# IO_Top_BOARD.net
KiCad netlist of a schematic drawn in EAGLE
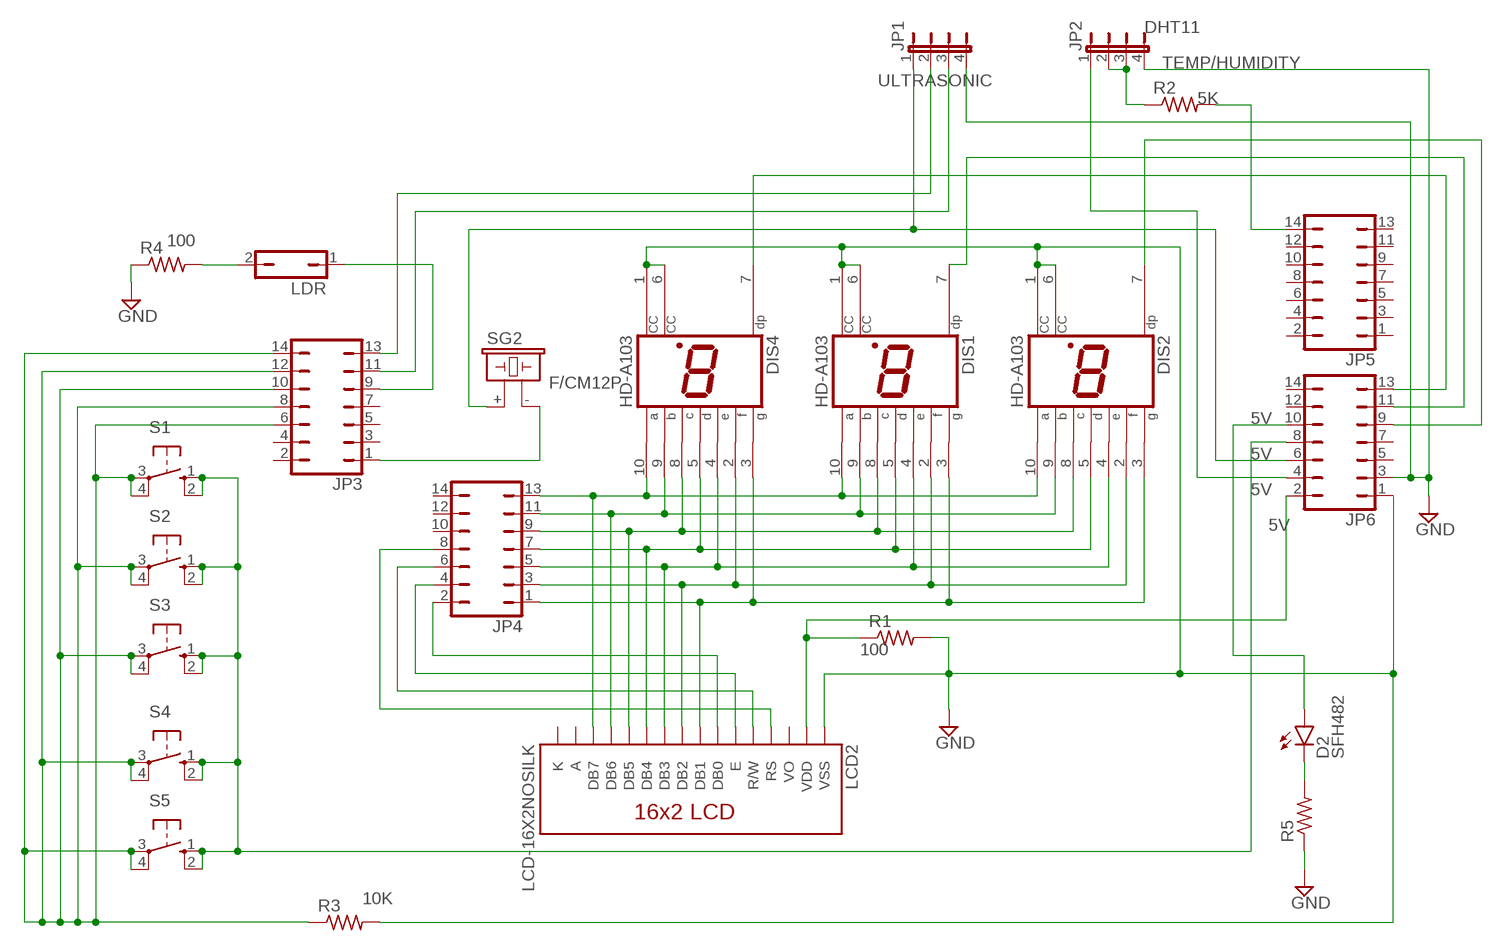
[diagram p0: schematic, sheet 1]

(export (version "E")
  (design (tool "Eeschema 10.0.6"))
  (components
    (comp (ref "D2")
      (value "SFH482")
      (footprint "eagle-import:SFH482")
      (libsource (lib "eagle-import") (part "SFH482"))
    )
    (comp (ref "DIS1")
      (value "HD-A103")
      (footprint "eagle-import:HDSP-A")
      (libsource (lib "eagle-import") (part "HD-A103"))
    )
    (comp (ref "DIS2")
      (value "HD-A103")
      (footprint "eagle-import:HDSP-A")
      (libsource (lib "eagle-import") (part "HD-A103"))
    )
    (comp (ref "DIS4")
      (value "HD-A103")
      (footprint "eagle-import:HDSP-A")
      (libsource (lib "eagle-import") (part "HD-A103"))
    )
    (comp (ref "JP1")
      (value "JP4E")
      (footprint "eagle-import:JP4")
      (libsource (lib "eagle-import") (part "JP4E"))
    )
    (comp (ref "JP2")
      (value "JP4E")
      (footprint "eagle-import:JP4")
      (libsource (lib "eagle-import") (part "JP4E"))
    )
    (comp (ref "JP3")
      (value "JP7Q")
      (footprint "eagle-import:JP7Q")
      (libsource (lib "eagle-import") (part "JP7Q"))
    )
    (comp (ref "JP4")
      (value "JP7Q")
      (footprint "eagle-import:JP7Q")
      (libsource (lib "eagle-import") (part "JP7Q"))
    )
    (comp (ref "JP5")
      (value "JP7Q")
      (footprint "eagle-import:JP7Q")
      (libsource (lib "eagle-import") (part "JP7Q"))
    )
    (comp (ref "JP6")
      (value "JP7Q")
      (footprint "eagle-import:JP7Q")
      (libsource (lib "eagle-import") (part "JP7Q"))
    )
    (comp (ref "LCD2")
      (value "LCD-16X2NOSILK")
      (footprint "eagle-import:LCD-16X2_NOSILK")
      (libsource (lib "eagle-import") (part "LCD-16X2NOSILK"))
    )
    (comp (ref "LDR")
      (value "JP1Q")
      (footprint "eagle-import:JP1")
      (libsource (lib "eagle-import") (part "JP1Q"))
    )
    (comp (ref "R1")
      (value "R-US_0204/2V")
      (footprint "eagle-import:0204V")
      (libsource (lib "eagle-import") (part "R-US_0204/2V"))
    )
    (comp (ref "R2")
      (value "R-US_0204/2V")
      (footprint "eagle-import:0204V")
      (libsource (lib "eagle-import") (part "R-US_0204/2V"))
    )
    (comp (ref "R3")
      (value "R-US_0204/2V")
      (footprint "eagle-import:0204V")
      (libsource (lib "eagle-import") (part "R-US_0204/2V"))
    )
    (comp (ref "R4")
      (value "R-US_0204/2V")
      (footprint "eagle-import:0204V")
      (libsource (lib "eagle-import") (part "R-US_0204/2V"))
    )
    (comp (ref "R5")
      (value "R-US_0204/2V")
      (footprint "eagle-import:0204V")
      (libsource (lib "eagle-import") (part "R-US_0204/2V"))
    )
    (comp (ref "S1")
      (value "10-XX")
      (footprint "eagle-import:B3F-10XX")
      (fields (field (name "MPN") "B3F-1000"))
      (libsource (lib "eagle-import") (part "10-XX"))
    )
    (comp (ref "S2")
      (value "10-XX")
      (footprint "eagle-import:B3F-10XX")
      (fields (field (name "MPN") "B3F-1000"))
      (libsource (lib "eagle-import") (part "10-XX"))
    )
    (comp (ref "S3")
      (value "10-XX")
      (footprint "eagle-import:B3F-10XX")
      (fields (field (name "MPN") "B3F-1000"))
      (libsource (lib "eagle-import") (part "10-XX"))
    )
    (comp (ref "S4")
      (value "10-XX")
      (footprint "eagle-import:B3F-10XX")
      (fields (field (name "MPN") "B3F-1000"))
      (libsource (lib "eagle-import") (part "10-XX"))
    )
    (comp (ref "S5")
      (value "10-XX")
      (footprint "eagle-import:B3F-10XX")
      (fields (field (name "MPN") "B3F-1000"))
      (libsource (lib "eagle-import") (part "10-XX"))
    )
    (comp (ref "SG2")
      (value "F/CM12P")
      (footprint "eagle-import:F_CM12P")
      (libsource (lib "eagle-import") (part "F/CM12P"))
    )
  )
  (nets
    (net (code "1") (name "/5V") (class "Default")
      (node (ref "JP1") (pin "1") (pinfunction "1_1") (pintype "passive"))
      (node (ref "JP6") (pin "6") (pinfunction "6_6") (pintype "passive"))
      (node (ref "SG2") (pin "+") (pinfunction "1_+") (pintype "passive"))
    )
    (net (code "2") (name "/A") (class "Default")
      (node (ref "LCD2") (pin "15") (pinfunction "A_15") (pintype "power_in"))
    )
    (net (code "3") (name "/K") (class "Default")
      (node (ref "LCD2") (pin "16") (pinfunction "K_16") (pintype "power_in"))
    )
    (net (code "4") (name "GND") (class "Default")
      (node (ref "DIS1") (pin "1") (pinfunction "CC_1") (pintype "passive"))
      (node (ref "DIS1") (pin "6") (pinfunction "CC_6") (pintype "passive"))
      (node (ref "DIS2") (pin "1") (pinfunction "CC_1") (pintype "passive"))
      (node (ref "DIS2") (pin "6") (pinfunction "CC_6") (pintype "passive"))
      (node (ref "DIS4") (pin "1") (pinfunction "CC_1") (pintype "passive"))
      (node (ref "DIS4") (pin "6") (pinfunction "CC_6") (pintype "passive"))
      (node (ref "JP1") (pin "4") (pinfunction "4_4") (pintype "passive"))
      (node (ref "JP2") (pin "4") (pinfunction "4_4") (pintype "passive"))
      (node (ref "JP6") (pin "1") (pinfunction "1_1") (pintype "passive"))
      (node (ref "JP6") (pin "3") (pinfunction "3_3") (pintype "passive"))
      (node (ref "LCD2") (pin "1") (pinfunction "VSS_1") (pintype "power_in"))
      (node (ref "R1") (pin "2") (pinfunction "2_2") (pintype "passive"))
      (node (ref "R3") (pin "2") (pinfunction "2_2") (pintype "passive"))
      (node (ref "R4") (pin "1") (pinfunction "1_1") (pintype "passive"))
      (node (ref "R5") (pin "1") (pinfunction "1_1") (pintype "passive"))
    )
    (net (code "5") (name "Net-(D2-C)") (class "Default")
      (node (ref "D2") (pin "K") (pinfunction "C_K") (pintype "passive"))
      (node (ref "R5") (pin "2") (pinfunction "2_2") (pintype "passive"))
    )
    (net (code "6") (name "Net-(D2-PadA)") (class "Default")
      (node (ref "D2") (pin "A") (pinfunction "A_A") (pintype "passive"))
      (node (ref "JP6") (pin "10") (pinfunction "10_10") (pintype "passive"))
    )
    (net (code "7") (name "Net-(DIS1-A)") (class "Default")
      (node (ref "DIS1") (pin "10") (pinfunction "A_10") (pintype "passive"))
      (node (ref "DIS2") (pin "10") (pinfunction "A_10") (pintype "passive"))
      (node (ref "DIS4") (pin "10") (pinfunction "A_10") (pintype "passive"))
      (node (ref "JP4") (pin "13") (pinfunction "13_13") (pintype "passive"))
      (node (ref "LCD2") (pin "14") (pinfunction "DB7_14") (pintype "bidirectional"))
    )
    (net (code "8") (name "Net-(DIS1-B)") (class "Default")
      (node (ref "DIS1") (pin "9") (pinfunction "B_9") (pintype "passive"))
      (node (ref "DIS2") (pin "9") (pinfunction "B_9") (pintype "passive"))
      (node (ref "DIS4") (pin "9") (pinfunction "B_9") (pintype "passive"))
      (node (ref "JP4") (pin "11") (pinfunction "11_11") (pintype "passive"))
      (node (ref "LCD2") (pin "13") (pinfunction "DB6_13") (pintype "bidirectional"))
    )
    (net (code "9") (name "Net-(DIS1-C)") (class "Default")
      (node (ref "DIS1") (pin "8") (pinfunction "C_8") (pintype "passive"))
      (node (ref "DIS2") (pin "8") (pinfunction "C_8") (pintype "passive"))
      (node (ref "DIS4") (pin "8") (pinfunction "C_8") (pintype "passive"))
      (node (ref "JP4") (pin "9") (pinfunction "9_9") (pintype "passive"))
      (node (ref "LCD2") (pin "12") (pinfunction "DB5_12") (pintype "bidirectional"))
    )
    (net (code "10") (name "Net-(DIS1-D)") (class "Default")
      (node (ref "DIS1") (pin "5") (pinfunction "D_5") (pintype "passive"))
      (node (ref "DIS2") (pin "5") (pinfunction "D_5") (pintype "passive"))
      (node (ref "DIS4") (pin "5") (pinfunction "D_5") (pintype "passive"))
      (node (ref "JP4") (pin "7") (pinfunction "7_7") (pintype "passive"))
      (node (ref "LCD2") (pin "11") (pinfunction "DB4_11") (pintype "bidirectional"))
    )
    (net (code "11") (name "Net-(DIS1-DP)") (class "Default")
      (node (ref "DIS1") (pin "7") (pinfunction "DP_7") (pintype "passive"))
      (node (ref "JP6") (pin "11") (pinfunction "11_11") (pintype "passive"))
    )
    (net (code "12") (name "Net-(DIS1-E)") (class "Default")
      (node (ref "DIS1") (pin "4") (pinfunction "E_4") (pintype "passive"))
      (node (ref "DIS2") (pin "4") (pinfunction "E_4") (pintype "passive"))
      (node (ref "DIS4") (pin "4") (pinfunction "E_4") (pintype "passive"))
      (node (ref "JP4") (pin "5") (pinfunction "5_5") (pintype "passive"))
      (node (ref "LCD2") (pin "10") (pinfunction "DB3_10") (pintype "bidirectional"))
    )
    (net (code "13") (name "Net-(DIS1-F)") (class "Default")
      (node (ref "DIS1") (pin "2") (pinfunction "F_2") (pintype "passive"))
      (node (ref "DIS2") (pin "2") (pinfunction "F_2") (pintype "passive"))
      (node (ref "DIS4") (pin "2") (pinfunction "F_2") (pintype "passive"))
      (node (ref "JP4") (pin "3") (pinfunction "3_3") (pintype "passive"))
      (node (ref "LCD2") (pin "9") (pinfunction "DB2_9") (pintype "bidirectional"))
    )
    (net (code "14") (name "Net-(DIS1-G)") (class "Default")
      (node (ref "DIS1") (pin "3") (pinfunction "G_3") (pintype "passive"))
      (node (ref "DIS2") (pin "3") (pinfunction "G_3") (pintype "passive"))
      (node (ref "DIS4") (pin "3") (pinfunction "G_3") (pintype "passive"))
      (node (ref "JP4") (pin "1") (pinfunction "1_1") (pintype "passive"))
      (node (ref "LCD2") (pin "8") (pinfunction "DB1_8") (pintype "bidirectional"))
    )
    (net (code "15") (name "Net-(DIS2-DP)") (class "Default")
      (node (ref "DIS2") (pin "7") (pinfunction "DP_7") (pintype "passive"))
      (node (ref "JP6") (pin "9") (pinfunction "9_9") (pintype "passive"))
    )
    (net (code "16") (name "Net-(DIS4-DP)") (class "Default")
      (node (ref "DIS4") (pin "7") (pinfunction "DP_7") (pintype "passive"))
      (node (ref "JP6") (pin "13") (pinfunction "13_13") (pintype "passive"))
    )
    (net (code "17") (name "Net-(JP1-Pad2)") (class "Default")
      (node (ref "JP1") (pin "2") (pinfunction "2_2") (pintype "passive"))
      (node (ref "JP3") (pin "13") (pinfunction "13_13") (pintype "passive"))
    )
    (net (code "18") (name "Net-(JP1-Pad3)") (class "Default")
      (node (ref "JP1") (pin "3") (pinfunction "3_3") (pintype "passive"))
      (node (ref "JP3") (pin "11") (pinfunction "11_11") (pintype "passive"))
    )
    (net (code "19") (name "Net-(JP2-Pad1)") (class "Default")
      (node (ref "JP2") (pin "1") (pinfunction "1_1") (pintype "passive"))
      (node (ref "JP6") (pin "4") (pinfunction "4_4") (pintype "passive"))
    )
    (net (code "20") (name "Net-(JP2-Pad2)") (class "Default")
      (node (ref "JP2") (pin "2") (pinfunction "2_2") (pintype "passive"))
      (node (ref "JP2") (pin "3") (pinfunction "3_3") (pintype "passive"))
      (node (ref "R2") (pin "1") (pinfunction "1_1") (pintype "passive"))
    )
    (net (code "21") (name "Net-(JP3-Pad9)") (class "Default")
      (node (ref "JP3") (pin "9") (pinfunction "9_9") (pintype "passive"))
      (node (ref "LDR") (pin "1") (pinfunction "1_1") (pintype "passive"))
    )
    (net (code "22") (name "Net-(JP5-Pad14)") (class "Default")
      (node (ref "JP5") (pin "14") (pinfunction "14_14") (pintype "passive"))
      (node (ref "R2") (pin "2") (pinfunction "2_2") (pintype "passive"))
    )
    (net (code "23") (name "Net-(LCD2-DB0)") (class "Default")
      (node (ref "JP4") (pin "2") (pinfunction "2_2") (pintype "passive"))
      (node (ref "LCD2") (pin "7") (pinfunction "DB0_7") (pintype "bidirectional"))
    )
    (net (code "24") (name "Net-(LCD2-E)") (class "Default")
      (node (ref "JP4") (pin "4") (pinfunction "4_4") (pintype "passive"))
      (node (ref "LCD2") (pin "6") (pinfunction "E_6") (pintype "input"))
    )
    (net (code "25") (name "Net-(LCD2-RS)") (class "Default")
      (node (ref "JP4") (pin "8") (pinfunction "8_8") (pintype "passive"))
      (node (ref "LCD2") (pin "4") (pinfunction "RS_4") (pintype "input"))
    )
    (net (code "26") (name "Net-(LCD2-R{slash}W)") (class "Default")
      (node (ref "JP4") (pin "6") (pinfunction "6_6") (pintype "passive"))
      (node (ref "LCD2") (pin "5") (pinfunction "R/W_5") (pintype "input"))
    )
    (net (code "27") (name "Net-(LCD2-VDD)") (class "Default")
      (node (ref "JP6") (pin "2") (pinfunction "2_2") (pintype "passive"))
      (node (ref "LCD2") (pin "2") (pinfunction "VDD_2") (pintype "power_in"))
      (node (ref "R1") (pin "1") (pinfunction "1_1") (pintype "passive"))
    )
    (net (code "28") (name "Net-(LDR-Pad2)") (class "Default")
      (node (ref "LDR") (pin "2") (pinfunction "2_2") (pintype "passive"))
      (node (ref "R4") (pin "2") (pinfunction "2_2") (pintype "passive"))
    )
    (net (code "29") (name "Net-(S1-P)") (class "Default")
      (node (ref "JP3") (pin "10") (pinfunction "10_10") (pintype "passive"))
      (node (ref "JP3") (pin "12") (pinfunction "12_12") (pintype "passive"))
      (node (ref "JP3") (pin "14") (pinfunction "14_14") (pintype "passive"))
      (node (ref "JP3") (pin "6") (pinfunction "6_6") (pintype "passive"))
      (node (ref "JP3") (pin "8") (pinfunction "8_8") (pintype "passive"))
      (node (ref "R3") (pin "1") (pinfunction "1_1") (pintype "passive"))
      (node (ref "S1") (pin "3") (pinfunction "P_3") (pintype "passive"))
      (node (ref "S1") (pin "4") (pinfunction "P1_4") (pintype "passive"))
      (node (ref "S2") (pin "3") (pinfunction "P_3") (pintype "passive"))
      (node (ref "S2") (pin "4") (pinfunction "P1_4") (pintype "passive"))
      (node (ref "S3") (pin "3") (pinfunction "P_3") (pintype "passive"))
      (node (ref "S3") (pin "4") (pinfunction "P1_4") (pintype "passive"))
      (node (ref "S4") (pin "3") (pinfunction "P_3") (pintype "passive"))
      (node (ref "S4") (pin "4") (pinfunction "P1_4") (pintype "passive"))
      (node (ref "S5") (pin "3") (pinfunction "P_3") (pintype "passive"))
      (node (ref "S5") (pin "4") (pinfunction "P1_4") (pintype "passive"))
    )
    (net (code "30") (name "Net-(S1-S)") (class "Default")
      (node (ref "JP6") (pin "8") (pinfunction "8_8") (pintype "passive"))
      (node (ref "S1") (pin "1") (pinfunction "S_1") (pintype "passive"))
      (node (ref "S1") (pin "2") (pinfunction "S1_2") (pintype "passive"))
      (node (ref "S2") (pin "1") (pinfunction "S_1") (pintype "passive"))
      (node (ref "S2") (pin "2") (pinfunction "S1_2") (pintype "passive"))
      (node (ref "S3") (pin "1") (pinfunction "S_1") (pintype "passive"))
      (node (ref "S3") (pin "2") (pinfunction "S1_2") (pintype "passive"))
      (node (ref "S4") (pin "1") (pinfunction "S_1") (pintype "passive"))
      (node (ref "S4") (pin "2") (pinfunction "S1_2") (pintype "passive"))
      (node (ref "S5") (pin "1") (pinfunction "S_1") (pintype "passive"))
      (node (ref "S5") (pin "2") (pinfunction "S1_2") (pintype "passive"))
    )
    (net (code "31") (name "Net-(SG2-2)") (class "Default")
      (node (ref "JP3") (pin "1") (pinfunction "1_1") (pintype "passive"))
      (node (ref "SG2") (pin "-") (pinfunction "2_-") (pintype "passive"))
    )
    (net (code "32") (name "unconnected-(JP3-Pad2)") (class "Default")
      (node (ref "JP3") (pin "2") (pinfunction "2_2") (pintype "passive"))
    )
    (net (code "33") (name "unconnected-(JP3-Pad3)") (class "Default")
      (node (ref "JP3") (pin "3") (pinfunction "3_3") (pintype "passive"))
    )
    (net (code "34") (name "unconnected-(JP3-Pad4)") (class "Default")
      (node (ref "JP3") (pin "4") (pinfunction "4_4") (pintype "passive"))
    )
    (net (code "35") (name "unconnected-(JP3-Pad5)") (class "Default")
      (node (ref "JP3") (pin "5") (pinfunction "5_5") (pintype "passive"))
    )
    (net (code "36") (name "unconnected-(JP3-Pad7)") (class "Default")
      (node (ref "JP3") (pin "7") (pinfunction "7_7") (pintype "passive"))
    )
    (net (code "37") (name "unconnected-(JP4-Pad10)") (class "Default")
      (node (ref "JP4") (pin "10") (pinfunction "10_10") (pintype "passive"))
    )
    (net (code "38") (name "unconnected-(JP4-Pad12)") (class "Default")
      (node (ref "JP4") (pin "12") (pinfunction "12_12") (pintype "passive"))
    )
    (net (code "39") (name "unconnected-(JP4-Pad14)") (class "Default")
      (node (ref "JP4") (pin "14") (pinfunction "14_14") (pintype "passive"))
    )
    (net (code "40") (name "unconnected-(JP5-Pad1)") (class "Default")
      (node (ref "JP5") (pin "1") (pinfunction "1_1") (pintype "passive"))
    )
    (net (code "41") (name "unconnected-(JP5-Pad2)") (class "Default")
      (node (ref "JP5") (pin "2") (pinfunction "2_2") (pintype "passive"))
    )
    (net (code "42") (name "unconnected-(JP5-Pad3)") (class "Default")
      (node (ref "JP5") (pin "3") (pinfunction "3_3") (pintype "passive"))
    )
    (net (code "43") (name "unconnected-(JP5-Pad4)") (class "Default")
      (node (ref "JP5") (pin "4") (pinfunction "4_4") (pintype "passive"))
    )
    (net (code "44") (name "unconnected-(JP5-Pad5)") (class "Default")
      (node (ref "JP5") (pin "5") (pinfunction "5_5") (pintype "passive"))
    )
    (net (code "45") (name "unconnected-(JP5-Pad6)") (class "Default")
      (node (ref "JP5") (pin "6") (pinfunction "6_6") (pintype "passive"))
    )
    (net (code "46") (name "unconnected-(JP5-Pad7)") (class "Default")
      (node (ref "JP5") (pin "7") (pinfunction "7_7") (pintype "passive"))
    )
    (net (code "47") (name "unconnected-(JP5-Pad8)") (class "Default")
      (node (ref "JP5") (pin "8") (pinfunction "8_8") (pintype "passive"))
    )
    (net (code "48") (name "unconnected-(JP5-Pad9)") (class "Default")
      (node (ref "JP5") (pin "9") (pinfunction "9_9") (pintype "passive"))
    )
    (net (code "49") (name "unconnected-(JP5-Pad10)") (class "Default")
      (node (ref "JP5") (pin "10") (pinfunction "10_10") (pintype "passive"))
    )
    (net (code "50") (name "unconnected-(JP5-Pad11)") (class "Default")
      (node (ref "JP5") (pin "11") (pinfunction "11_11") (pintype "passive"))
    )
    (net (code "51") (name "unconnected-(JP5-Pad12)") (class "Default")
      (node (ref "JP5") (pin "12") (pinfunction "12_12") (pintype "passive"))
    )
    (net (code "52") (name "unconnected-(JP5-Pad13)") (class "Default")
      (node (ref "JP5") (pin "13") (pinfunction "13_13") (pintype "passive"))
    )
    (net (code "53") (name "unconnected-(JP6-Pad5)") (class "Default")
      (node (ref "JP6") (pin "5") (pinfunction "5_5") (pintype "passive"))
    )
    (net (code "54") (name "unconnected-(JP6-Pad7)") (class "Default")
      (node (ref "JP6") (pin "7") (pinfunction "7_7") (pintype "passive"))
    )
    (net (code "55") (name "unconnected-(JP6-Pad12)") (class "Default")
      (node (ref "JP6") (pin "12") (pinfunction "12_12") (pintype "passive"))
    )
    (net (code "56") (name "unconnected-(JP6-Pad14)") (class "Default")
      (node (ref "JP6") (pin "14") (pinfunction "14_14") (pintype "passive"))
    )
    (net (code "57") (name "unconnected-(LCD2-VO-Pad3)") (class "Default")
      (node (ref "LCD2") (pin "3") (pinfunction "VO_3") (pintype "bidirectional"))
    )
  )
)
